# mpc57_cwconn.net
KiCad netlist of a schematic drawn in Altium Designer
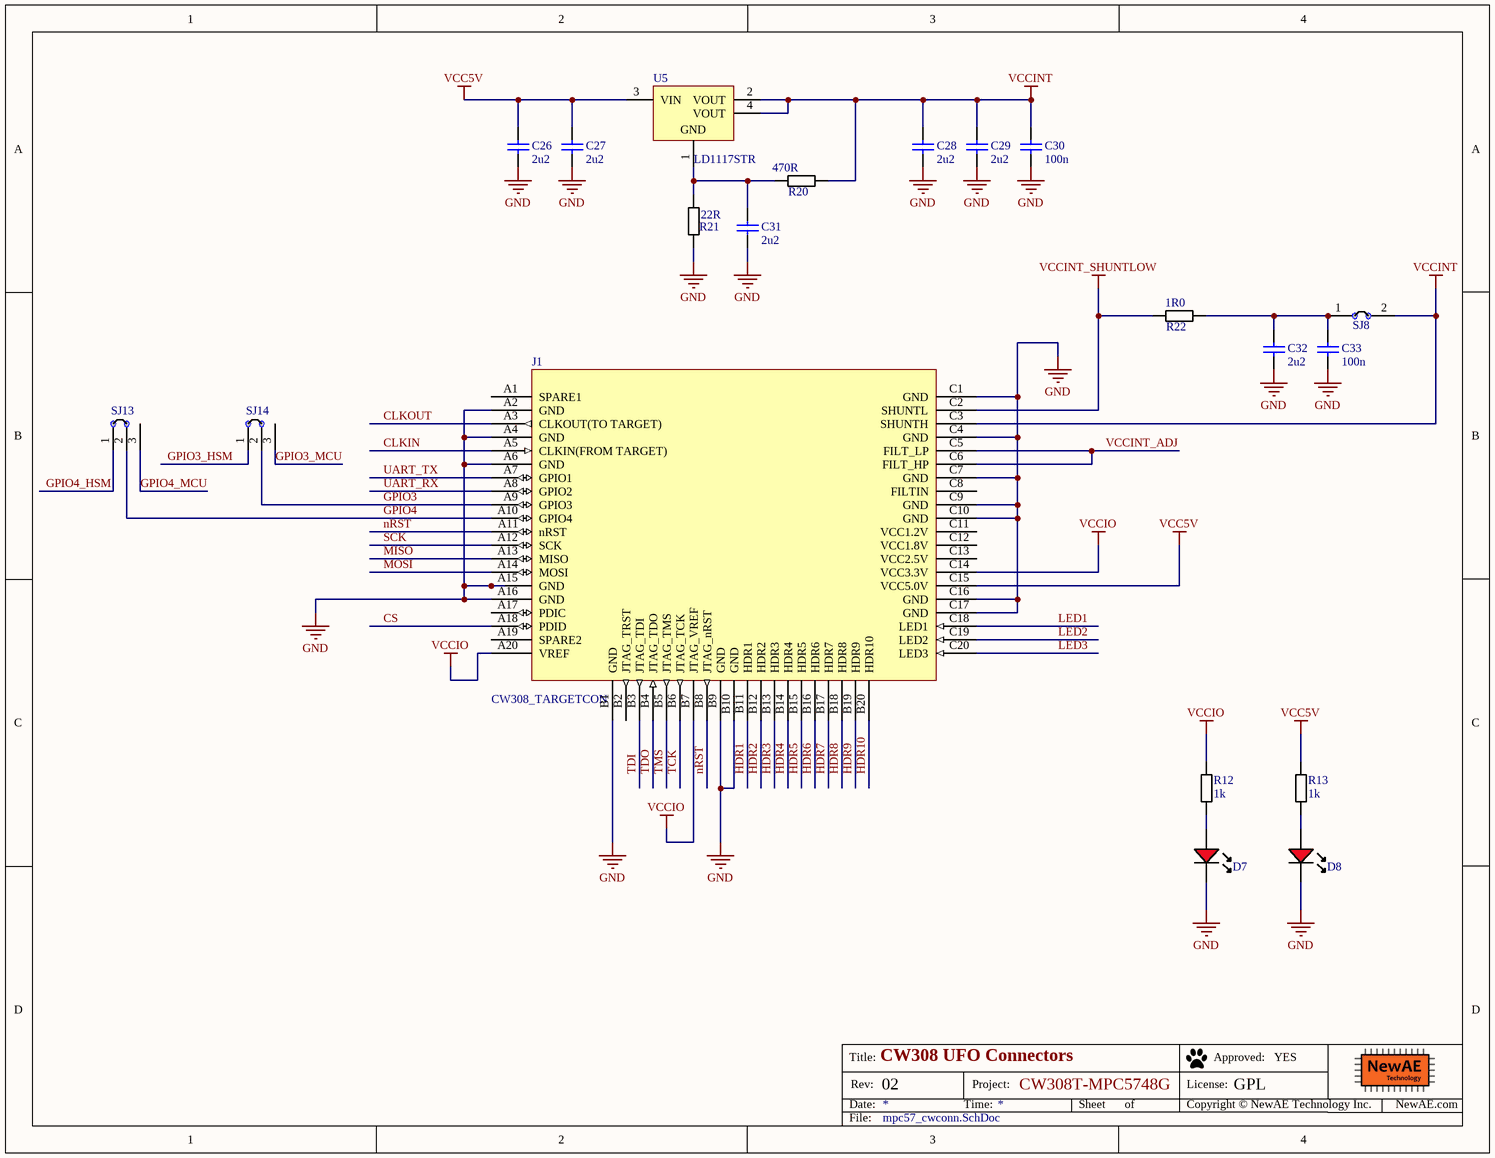
[diagram p0: mpc57_cwconn.SchDoc]

(export (version "E")
  (design (tool "Eeschema 10.0.6"))
  (components
    (comp (ref "C26")
      (value "2u2")
      (footprint "CAPC0603_M")
      (description "2u2, 0603")
      (fields (field (name "PART NUMBER") "CCHIP-2u2-0603"))
      (libsource (lib "NewAE_AltiumLib") (part "CAP"))
    )
    (comp (ref "C27")
      (value "2u2")
      (footprint "CAPC0603_M")
      (description "2u2, 0603")
      (fields (field (name "PART NUMBER") "CCHIP-2u2-0603"))
      (libsource (lib "NewAE_AltiumLib") (part "CAP"))
    )
    (comp (ref "C28")
      (value "2u2")
      (footprint "CAPC0603_M")
      (description "2u2, 0603")
      (fields (field (name "PART NUMBER") "CCHIP-2u2-0603"))
      (libsource (lib "NewAE_AltiumLib") (part "CAP"))
    )
    (comp (ref "C29")
      (value "2u2")
      (footprint "CAPC0603_M")
      (description "2u2, 0603")
      (fields (field (name "PART NUMBER") "CCHIP-2u2-0603"))
      (libsource (lib "NewAE_AltiumLib") (part "CAP"))
    )
    (comp (ref "C30")
      (value "100n")
      (footprint "CAPC0402_M")
      (description "100n, 0402")
      (fields (field (name "PART NUMBER") "CCHIP-100n-0402"))
      (libsource (lib "NewAE_AltiumLib") (part "CAP"))
    )
    (comp (ref "C31")
      (value "2u2")
      (footprint "CAPC0603_M")
      (description "2u2, 0603")
      (fields (field (name "PART NUMBER") "CCHIP-2u2-0603"))
      (libsource (lib "NewAE_AltiumLib") (part "CAP"))
    )
    (comp (ref "C32")
      (value "2u2")
      (footprint "CAPC0603_M")
      (description "2u2, 0603")
      (fields (field (name "PART NUMBER") "CCHIP-2u2-0603"))
      (libsource (lib "NewAE_AltiumLib") (part "CAP"))
    )
    (comp (ref "C33")
      (value "100n")
      (footprint "CAPC0402_M")
      (description "100n, 0402")
      (fields (field (name "PART NUMBER") "CCHIP-100n-0402"))
      (libsource (lib "NewAE_AltiumLib") (part "CAP"))
    )
    (comp (ref "D7")
      (value "LED, 0603, Red")
      (footprint "LED-0603-RED")
      (description "Chip LED, Red")
      (fields (field (name "PART NUMBER") "LEDCHIP_0603_RED"))
      (libsource (lib "NewAE_AltiumLib") (part "LED_RED"))
    )
    (comp (ref "D8")
      (value "LED, 0603, Red")
      (footprint "LED-0603-RED")
      (description "Chip LED, Red")
      (fields (field (name "PART NUMBER") "LEDCHIP_0603_RED"))
      (libsource (lib "NewAE_AltiumLib") (part "LED_RED"))
    )
    (comp (ref "J1")
      (value "CW308_TARGETCON")
      (footprint "ChipWhisperer_AltiumLib:CW308_TBOARD_CONN")
      (description "CW308 \"Standard\" Target Board Connector")
      (libsource (lib "ChipWhisperer_AltiumLib") (part "CW308_TBOARD"))
    )
    (comp (ref "R12")
      (value "1k")
      (footprint "RESC1608X55N")
      (description "1k res, 0603, 1%, 1/10W")
      (fields (field (name "PART NUMBER") "RCHIP-1K-0603") (field (name "TOLERANCE") "1%"))
      (libsource (lib "NewAE_AltiumLib") (part "RES-EU"))
    )
    (comp (ref "R13")
      (value "1k")
      (footprint "RESC1608X55N")
      (description "1k res, 0603, 1%, 1/10W")
      (fields (field (name "PART NUMBER") "RCHIP-1K-0603") (field (name "TOLERANCE") "1%"))
      (libsource (lib "NewAE_AltiumLib") (part "RES-EU"))
    )
    (comp (ref "R20")
      (value "470R")
      (footprint "RESC1608X55N")
      (description "470R res, 0603, 1%, 1/10W")
      (fields (field (name "PART NUMBER") "RCHIP-120R-0603") (field (name "TOLERANCE") "1%"))
      (libsource (lib "") (part "RES-EU_1"))
    )
    (comp (ref "R21")
      (value "22R")
      (footprint "RESC1608X55N")
      (description "120R res, 0603, 1%, 1/10W")
      (fields (field (name "PART NUMBER") "RCHIP-120R-0603") (field (name "TOLERANCE") "1%"))
      (libsource (lib "NewAE_AltiumLib") (part "RES-EU"))
    )
    (comp (ref "R22")
      (value "1R0")
      (footprint "RESC2012X70N")
      (description "1R0 res, 0805, 1%, 1/8W")
      (fields (field (name "PART NUMBER") "RCHIP-1R0-0805") (field (name "TOLERANCE") "1%"))
      (libsource (lib "") (part "RES-EU_2"))
    )
    (comp (ref "SJ8")
      (value "NC")
      (footprint "SJ_2S_NC")
      (description "Solder Jumper, NC")
      (fields (field (name "PART NUMBER") "SJ_2S"))
      (libsource (lib "NewAE_AltiumLib") (part "SJ_2S"))
    )
    (comp (ref "SJ13")
      (value "NC")
      (footprint "SJ_3S_NC12")
      (description "Solder Jumper, NC")
      (fields (field (name "PART NUMBER") "SJ_3S_12JMP"))
      (libsource (lib "NewAE_AltiumLib") (part "SJ_3S_12JMP"))
    )
    (comp (ref "SJ14")
      (value "NC")
      (footprint "SJ_3S_NC12")
      (description "Solder Jumper, NC")
      (fields (field (name "PART NUMBER") "SJ_3S_12JMP"))
      (libsource (lib "NewAE_AltiumLib") (part "SJ_3S_12JMP"))
    )
    (comp (ref "U5")
      (value "LD1117STR")
      (footprint "SOT-223_L")
      (description "Adjustable Low Drop Voltage Regulator, 1.25 to 15V, 4-Pin SOT-223, Tape and Reel")
      (libsource (lib "Altium Content Vault") (part "CMP-0244-00313-1"))
    )
  )
  (nets
    (net (code "1") (name "/CLKIN") (class "Default")
      (node (ref "J1") (pin "A5") (pinfunction "CLKIN(FROM_TARGET)_A5") (pintype "input"))
    )
    (net (code "2") (name "/CLKOUT") (class "Default")
      (node (ref "J1") (pin "A3") (pinfunction "CLKOUT(TO_TARGET)_A3") (pintype "output"))
    )
    (net (code "3") (name "/CS") (class "Default")
      (node (ref "J1") (pin "A18") (pinfunction "PDID_A18") (pintype "bidirectional"))
    )
    (net (code "4") (name "/GPIO3") (class "Default")
      (node (ref "J1") (pin "A9") (pinfunction "GPIO3_A9") (pintype "bidirectional"))
      (node (ref "SJ14") (pin "2") (pinfunction "2_2") (pintype "passive"))
    )
    (net (code "5") (name "/GPIO3_HSM") (class "Default")
      (node (ref "SJ14") (pin "1") (pinfunction "1_1") (pintype "passive"))
    )
    (net (code "6") (name "/GPIO3_MCU") (class "Default")
      (node (ref "SJ14") (pin "3") (pinfunction "3_3") (pintype "passive"))
    )
    (net (code "7") (name "/GPIO4") (class "Default")
      (node (ref "J1") (pin "A10") (pinfunction "GPIO4_A10") (pintype "bidirectional"))
      (node (ref "SJ13") (pin "2") (pinfunction "2_2") (pintype "passive"))
    )
    (net (code "8") (name "/GPIO4_HSM") (class "Default")
      (node (ref "SJ13") (pin "1") (pinfunction "1_1") (pintype "passive"))
    )
    (net (code "9") (name "/GPIO4_MCU") (class "Default")
      (node (ref "SJ13") (pin "3") (pinfunction "3_3") (pintype "passive"))
    )
    (net (code "10") (name "/HDR1") (class "Default")
      (node (ref "J1") (pin "B11") (pinfunction "HDR1_B11") (pintype "passive"))
    )
    (net (code "11") (name "/HDR2") (class "Default")
      (node (ref "J1") (pin "B12") (pinfunction "HDR2_B12") (pintype "passive"))
    )
    (net (code "12") (name "/HDR3") (class "Default")
      (node (ref "J1") (pin "B13") (pinfunction "HDR3_B13") (pintype "passive"))
    )
    (net (code "13") (name "/HDR4") (class "Default")
      (node (ref "J1") (pin "B14") (pinfunction "HDR4_B14") (pintype "passive"))
    )
    (net (code "14") (name "/HDR5") (class "Default")
      (node (ref "J1") (pin "B15") (pinfunction "HDR5_B15") (pintype "passive"))
    )
    (net (code "15") (name "/HDR6") (class "Default")
      (node (ref "J1") (pin "B16") (pinfunction "HDR6_B16") (pintype "passive"))
    )
    (net (code "16") (name "/HDR7") (class "Default")
      (node (ref "J1") (pin "B17") (pinfunction "HDR7_B17") (pintype "passive"))
    )
    (net (code "17") (name "/HDR8") (class "Default")
      (node (ref "J1") (pin "B18") (pinfunction "HDR8_B18") (pintype "passive"))
    )
    (net (code "18") (name "/HDR9") (class "Default")
      (node (ref "J1") (pin "B19") (pinfunction "HDR9_B19") (pintype "passive"))
    )
    (net (code "19") (name "/HDR10") (class "Default")
      (node (ref "J1") (pin "B20") (pinfunction "HDR10_B20") (pintype "passive"))
    )
    (net (code "20") (name "/LED1") (class "Default")
      (node (ref "J1") (pin "C18") (pinfunction "LED1_C18") (pintype "input"))
    )
    (net (code "21") (name "/LED2") (class "Default")
      (node (ref "J1") (pin "C19") (pinfunction "LED2_C19") (pintype "input"))
    )
    (net (code "22") (name "/LED3") (class "Default")
      (node (ref "J1") (pin "C20") (pinfunction "LED3_C20") (pintype "input"))
    )
    (net (code "23") (name "/MISO") (class "Default")
      (node (ref "J1") (pin "A13") (pinfunction "MISO_A13") (pintype "bidirectional"))
    )
    (net (code "24") (name "/MOSI") (class "Default")
      (node (ref "J1") (pin "A14") (pinfunction "MOSI_A14") (pintype "bidirectional"))
    )
    (net (code "25") (name "/SCK") (class "Default")
      (node (ref "J1") (pin "A12") (pinfunction "SCK_A12") (pintype "bidirectional"))
    )
    (net (code "26") (name "/TCK") (class "Default")
      (node (ref "J1") (pin "B6") (pinfunction "JTAG_TCK_B6") (pintype "output"))
    )
    (net (code "27") (name "/TDI") (class "Default")
      (node (ref "J1") (pin "B3") (pinfunction "JTAG_TDI_B3") (pintype "output"))
    )
    (net (code "28") (name "/TDO") (class "Default")
      (node (ref "J1") (pin "B4") (pinfunction "JTAG_TDO_B4") (pintype "input"))
    )
    (net (code "29") (name "/TMS") (class "Default")
      (node (ref "J1") (pin "B5") (pinfunction "JTAG_TMS_B5") (pintype "output"))
    )
    (net (code "30") (name "/UART_RX") (class "Default")
      (node (ref "J1") (pin "A8") (pinfunction "GPIO2_A8") (pintype "bidirectional"))
    )
    (net (code "31") (name "/UART_TX") (class "Default")
      (node (ref "J1") (pin "A7") (pinfunction "GPIO1_A7") (pintype "bidirectional"))
    )
    (net (code "32") (name "/VCCINT_ADJ") (class "Default")
      (node (ref "J1") (pin "C5") (pinfunction "FILT_LP_C5") (pintype "passive"))
      (node (ref "J1") (pin "C6") (pinfunction "FILT_HP_C6") (pintype "passive"))
    )
    (net (code "33") (name "/nRST") (class "Default")
      (node (ref "J1") (pin "A11") (pinfunction "nRST_A11") (pintype "bidirectional"))
      (node (ref "J1") (pin "B8") (pinfunction "JTAG_nRST_B8") (pintype "output"))
    )
    (net (code "34") (name "GND") (class "Default")
      (node (ref "C26") (pin "2") (pinfunction "2_2") (pintype "passive"))
      (node (ref "C27") (pin "2") (pinfunction "2_2") (pintype "passive"))
      (node (ref "C28") (pin "2") (pinfunction "2_2") (pintype "passive"))
      (node (ref "C29") (pin "2") (pinfunction "2_2") (pintype "passive"))
      (node (ref "C30") (pin "2") (pinfunction "2_2") (pintype "passive"))
      (node (ref "C31") (pin "2") (pinfunction "2_2") (pintype "passive"))
      (node (ref "C32") (pin "2") (pinfunction "2_2") (pintype "passive"))
      (node (ref "C33") (pin "2") (pinfunction "2_2") (pintype "passive"))
      (node (ref "D7") (pin "K") (pinfunction "K_K") (pintype "passive"))
      (node (ref "D8") (pin "K") (pinfunction "K_K") (pintype "passive"))
      (node (ref "J1") (pin "A15") (pinfunction "GND_A15") (pintype "passive"))
      (node (ref "J1") (pin "A16") (pinfunction "GND_A16") (pintype "passive"))
      (node (ref "J1") (pin "A2") (pinfunction "GND_A2") (pintype "passive"))
      (node (ref "J1") (pin "A4") (pinfunction "GND_A4") (pintype "passive"))
      (node (ref "J1") (pin "A6") (pinfunction "GND_A6") (pintype "power_in"))
      (node (ref "J1") (pin "B1") (pinfunction "GND_B1") (pintype "passive"))
      (node (ref "J1") (pin "B10") (pinfunction "GND_B10") (pintype "passive"))
      (node (ref "J1") (pin "B9") (pinfunction "GND_B9") (pintype "passive"))
      (node (ref "J1") (pin "C1") (pinfunction "GND_C1") (pintype "power_in"))
      (node (ref "J1") (pin "C10") (pinfunction "GND_C10") (pintype "power_in"))
      (node (ref "J1") (pin "C16") (pinfunction "GND_C16") (pintype "power_in"))
      (node (ref "J1") (pin "C17") (pinfunction "GND_C17") (pintype "power_in"))
      (node (ref "J1") (pin "C4") (pinfunction "GND_C4") (pintype "power_in"))
      (node (ref "J1") (pin "C7") (pinfunction "GND_C7") (pintype "power_in"))
      (node (ref "J1") (pin "C9") (pinfunction "GND_C9") (pintype "power_in"))
      (node (ref "R21") (pin "2") (pinfunction "2_2") (pintype "passive"))
    )
    (net (code "35") (name "Net-(C32-Pad1)") (class "Default")
      (node (ref "C32") (pin "1") (pinfunction "1_1") (pintype "passive"))
      (node (ref "C33") (pin "1") (pinfunction "1_1") (pintype "passive"))
      (node (ref "R22") (pin "2") (pinfunction "2_2") (pintype "passive"))
      (node (ref "SJ8") (pin "1") (pinfunction "1_1") (pintype "passive"))
    )
    (net (code "36") (name "Net-(D7-PadA)") (class "Default")
      (node (ref "D7") (pin "A") (pinfunction "A_A") (pintype "passive"))
      (node (ref "R12") (pin "2") (pinfunction "2_2") (pintype "passive"))
    )
    (net (code "37") (name "Net-(D8-PadA)") (class "Default")
      (node (ref "D8") (pin "A") (pinfunction "A_A") (pintype "passive"))
      (node (ref "R13") (pin "2") (pinfunction "2_2") (pintype "passive"))
    )
    (net (code "38") (name "Net-(U5-GND)") (class "Default")
      (node (ref "C31") (pin "1") (pinfunction "1_1") (pintype "passive"))
      (node (ref "R20") (pin "2") (pinfunction "2_2") (pintype "passive"))
      (node (ref "R21") (pin "1") (pinfunction "1_1") (pintype "passive"))
      (node (ref "U5") (pin "1") (pinfunction "GND_1") (pintype "power_in"))
    )
    (net (code "39") (name "VCC5V") (class "Default")
      (node (ref "C26") (pin "1") (pinfunction "1_1") (pintype "passive"))
      (node (ref "C27") (pin "1") (pinfunction "1_1") (pintype "passive"))
      (node (ref "J1") (pin "C15") (pinfunction "VCC5.0V_C15") (pintype "power_in"))
      (node (ref "R13") (pin "1") (pinfunction "1_1") (pintype "passive"))
      (node (ref "U5") (pin "3") (pinfunction "VIN_3") (pintype "power_in"))
    )
    (net (code "40") (name "VCCINT") (class "Default")
      (node (ref "C28") (pin "1") (pinfunction "1_1") (pintype "passive"))
      (node (ref "C29") (pin "1") (pinfunction "1_1") (pintype "passive"))
      (node (ref "C30") (pin "1") (pinfunction "1_1") (pintype "passive"))
      (node (ref "J1") (pin "C3") (pinfunction "SHUNTH_C3") (pintype "passive"))
      (node (ref "R20") (pin "1") (pinfunction "1_1") (pintype "passive"))
      (node (ref "SJ8") (pin "2") (pinfunction "2_2") (pintype "passive"))
      (node (ref "U5") (pin "2") (pinfunction "VOUT_2") (pintype "power_in"))
      (node (ref "U5") (pin "4") (pinfunction "VOUT_4") (pintype "power_in"))
    )
    (net (code "41") (name "VCCINT_SHUNTLOW") (class "Default")
      (node (ref "J1") (pin "C2") (pinfunction "SHUNTL_C2") (pintype "passive"))
      (node (ref "R22") (pin "1") (pinfunction "1_1") (pintype "passive"))
    )
    (net (code "42") (name "VCCIO") (class "Default")
      (node (ref "J1") (pin "A20") (pinfunction "VREF_A20") (pintype "tri_state"))
      (node (ref "J1") (pin "B7") (pinfunction "JTAG_VREF_B7") (pintype "tri_state"))
      (node (ref "J1") (pin "C14") (pinfunction "VCC3.3V_C14") (pintype "power_in"))
      (node (ref "R12") (pin "1") (pinfunction "1_1") (pintype "passive"))
    )
    (net (code "43") (name "unconnected-(J1-FILTIN-PadC8)") (class "Default")
      (node (ref "J1") (pin "C8") (pinfunction "FILTIN_C8") (pintype "passive"))
    )
    (net (code "44") (name "unconnected-(J1-JTAG_TRST-PadB2)") (class "Default")
      (node (ref "J1") (pin "B2") (pinfunction "JTAG_TRST_B2") (pintype "output"))
    )
    (net (code "45") (name "unconnected-(J1-PDIC-PadA17)") (class "Default")
      (node (ref "J1") (pin "A17") (pinfunction "PDIC_A17") (pintype "bidirectional"))
    )
    (net (code "46") (name "unconnected-(J1-SPARE1-PadA1)") (class "Default")
      (node (ref "J1") (pin "A1") (pinfunction "SPARE1_A1") (pintype "passive"))
    )
    (net (code "47") (name "unconnected-(J1-SPARE2-PadA19)") (class "Default")
      (node (ref "J1") (pin "A19") (pinfunction "SPARE2_A19") (pintype "passive"))
    )
    (net (code "48") (name "unconnected-(J1-VCC1.2V-PadC11)") (class "Default")
      (node (ref "J1") (pin "C11") (pinfunction "VCC1.2V_C11") (pintype "power_in"))
    )
    (net (code "49") (name "unconnected-(J1-VCC1.8V-PadC12)") (class "Default")
      (node (ref "J1") (pin "C12") (pinfunction "VCC1.8V_C12") (pintype "power_in"))
    )
    (net (code "50") (name "unconnected-(J1-VCC2.5V-PadC13)") (class "Default")
      (node (ref "J1") (pin "C13") (pinfunction "VCC2.5V_C13") (pintype "power_in"))
    )
  )
)
